# ProPrj_WirelessUWB_2025-08-06.net
KiCad netlist of a schematic drawn in EasyEDA Pro
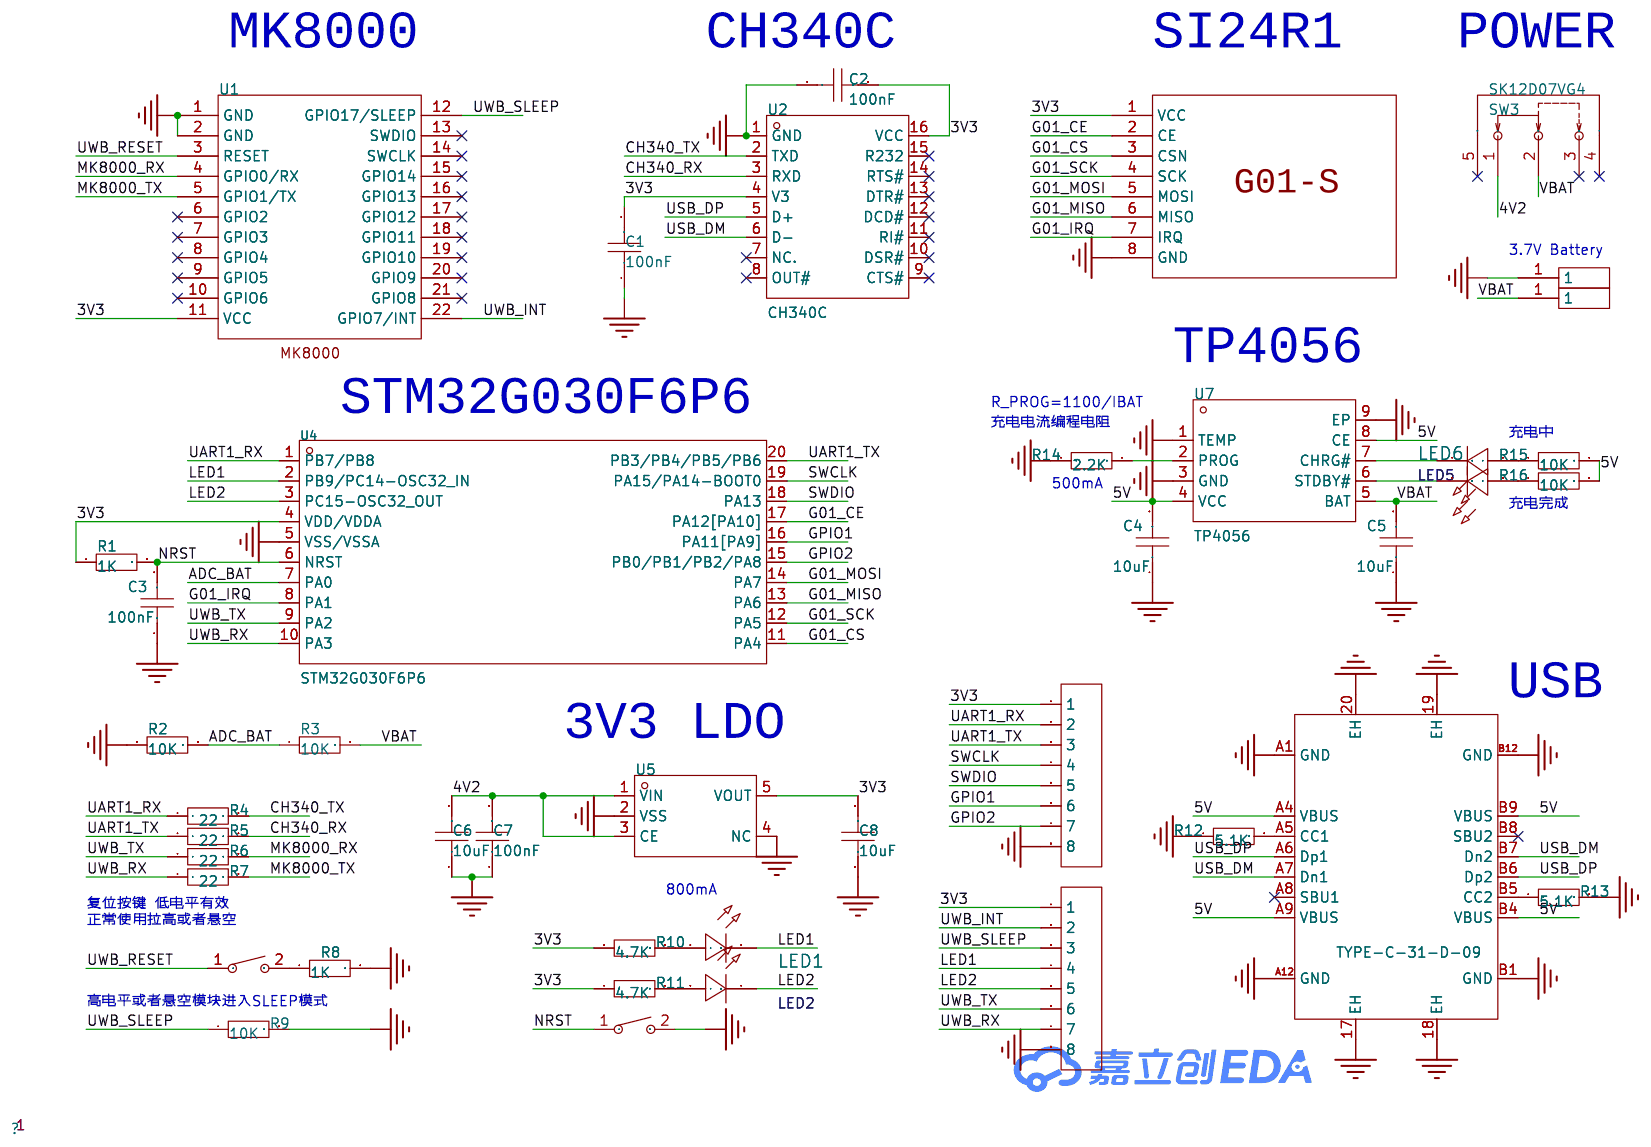
[diagram p0: schematic sheet]

(export (version "E")
  (design (tool "Eeschema 10.0.6"))
  (components
    (comp (ref "C1")
      (value "100nF")
      (footprint "easyedapro:C0603")
      (libsource (lib "easyedapro") (part "CapAcitance"))
    )
    (comp (ref "C2")
      (value "100nF")
      (footprint "easyedapro:C0603")
      (libsource (lib "easyedapro") (part "CapAcitance"))
    )
    (comp (ref "C3")
      (value "100nF")
      (footprint "easyedapro:C0603")
      (libsource (lib "easyedapro") (part "CapAcitance"))
    )
    (comp (ref "C4")
      (value "10uF")
      (footprint "easyedapro:C0603")
      (fields
        (field (name "Manufacturer Part") "CL10A106KP8NNNC")
        (field (name "Manufacturer") "SAMSUNG(三星)")
      )
      (libsource (lib "easyedapro") (part "CapAcitance"))
    )
    (comp (ref "C5")
      (value "10uF")
      (footprint "easyedapro:C0603")
      (fields
        (field (name "Manufacturer Part") "CL10A106KP8NNNC")
        (field (name "Manufacturer") "SAMSUNG(三星)")
      )
      (libsource (lib "easyedapro") (part "CapAcitance"))
    )
    (comp (ref "C6")
      (value "10uF")
      (footprint "easyedapro:C0603")
      (libsource (lib "easyedapro") (part "CapAcitance"))
    )
    (comp (ref "C7")
      (value "100nF")
      (footprint "easyedapro:C0603")
      (libsource (lib "easyedapro") (part "CapAcitance"))
    )
    (comp (ref "C8")
      (value "10uF")
      (footprint "easyedapro:C0603")
      (libsource (lib "easyedapro") (part "CapAcitance"))
    )
    (comp (ref "H1")
      (value "~")
      (footprint "easyedapro:HDR-TH_8P-P2.54-V-F-1")
      (libsource (lib "easyedapro") (part "Header-Female-2.54_1x8"))
    )
    (comp (ref "H2")
      (value "~")
      (footprint "easyedapro:HDR-TH_8P-P2.54-V-F-1")
      (libsource (lib "easyedapro") (part "Header-Female-2.54_1x8"))
    )
    (comp (ref "LED1")
      (value "~")
      (footprint "easyedapro:LED_0603")
      (libsource (lib "easyedapro") (part "LED_R"))
    )
    (comp (ref "LED2")
      (value "~")
      (footprint "easyedapro:LED_0603")
      (libsource (lib "easyedapro") (part "LED_B"))
    )
    (comp (ref "LED5")
      (value "~")
      (footprint "easyedapro:LED_0603")
      (libsource (lib "easyedapro") (part "LED_G"))
    )
    (comp (ref "LED6")
      (value "~")
      (footprint "easyedapro:LED_0603")
      (libsource (lib "easyedapro") (part "LED_R"))
    )
    (comp (ref "R1") (value "1K") (footprint "easyedapro:R0603") (libsource (lib "easyedapro") (part "电阻")))
    (comp (ref "R2") (value "10K") (footprint "easyedapro:R0603") (libsource (lib "easyedapro") (part "电阻")))
    (comp (ref "R3") (value "10K") (footprint "easyedapro:R0603") (libsource (lib "easyedapro") (part "电阻")))
    (comp (ref "R4") (value "22") (footprint "easyedapro:R0603") (libsource (lib "easyedapro") (part "电阻")))
    (comp (ref "R5") (value "22") (footprint "easyedapro:R0603") (libsource (lib "easyedapro") (part "电阻")))
    (comp (ref "R6") (value "22") (footprint "easyedapro:R0603") (libsource (lib "easyedapro") (part "电阻")))
    (comp (ref "R7") (value "22") (footprint "easyedapro:R0603") (libsource (lib "easyedapro") (part "电阻")))
    (comp (ref "R8") (value "1K") (footprint "easyedapro:R0603") (libsource (lib "easyedapro") (part "电阻")))
    (comp (ref "R9") (value "10K") (footprint "easyedapro:R0603") (libsource (lib "easyedapro") (part "电阻")))
    (comp (ref "R10") (value "4.7K") (libsource (lib "easyedapro") (part "电阻")))
    (comp (ref "R11") (value "4.7K") (libsource (lib "easyedapro") (part "电阻")))
    (comp (ref "R12")
      (value "5.1K")
      (footprint "easyedapro:R0603")
      (fields
        (field (name "Manufacturer Part") "0603WAF5101T5E")
        (field (name "Manufacturer") "UNI-ROYAL(厚声)")
      )
      (libsource (lib "easyedapro") (part "电阻"))
    )
    (comp (ref "R13")
      (value "5.1K")
      (footprint "easyedapro:R0603")
      (fields
        (field (name "Manufacturer Part") "0603WAF5101T5E")
        (field (name "Manufacturer") "UNI-ROYAL(厚声)")
      )
      (libsource (lib "easyedapro") (part "电阻"))
    )
    (comp (ref "R14")
      (value "2.2K")
      (footprint "easyedapro:R0603")
      (fields
        (field (name "Manufacturer Part") "0603WAF2201T5E")
        (field (name "Manufacturer") "UNI-ROYAL(厚声)")
      )
      (libsource (lib "easyedapro") (part "电阻"))
    )
    (comp (ref "R15")
      (value "10K")
      (footprint "easyedapro:R0603")
      (fields
        (field (name "Manufacturer Part") "0603WAF1002T5E")
        (field (name "Manufacturer") "UNI-ROYAL(厚声)")
      )
      (libsource (lib "easyedapro") (part "电阻"))
    )
    (comp (ref "R16")
      (value "10K")
      (footprint "easyedapro:R0603")
      (fields
        (field (name "Manufacturer Part") "0603WAF1002T5E")
        (field (name "Manufacturer") "UNI-ROYAL(厚声)")
      )
      (libsource (lib "easyedapro") (part "电阻"))
    )
    (comp (ref "SW1")
      (value "TS342A2P-WZ")
      (footprint "easyedapro:SW-SMD_L4.0-W2.9-LS5.0")
      (fields (field (name "Manufacturer") "SHOU HAN(首韩)"))
      (libsource (lib "easyedapro") (part "TS342A2P-WZ"))
    )
    (comp (ref "SW2")
      (value "TS342A2P-WZ")
      (footprint "easyedapro:SW-SMD_L4.0-W2.9-LS5.0")
      (fields (field (name "Manufacturer") "SHOU HAN(首韩)"))
      (libsource (lib "easyedapro") (part "TS342A2P-WZ"))
    )
    (comp (ref "SW3")
      (value "SK12D07VG4")
      (footprint "easyedapro:SW-TH_SK12D07VG4")
      (description "电路结构:单刀双掷;安装方式:-;额定电流(DC):500mA;额定电压(DC):50V;额定电流(AC):-;额定电压(AC):-;机械寿命:5千次;")
      (fields (field (name "Manufacturer") "SHOU HAN(首韩)"))
      (libsource (lib "easyedapro") (part "SK12D07VG4"))
    )
    (comp (ref "U1")
      (value "~")
      (footprint "easyedapro:MK8000")
      (description "UWB模块")
      (libsource (lib "easyedapro") (part "MK8000"))
    )
    (comp (ref "U2")
      (value "CH340C")
      (footprint "easyedapro:SOP-16_L10.0-W3.9-P1.27-LS6.0-BL")
      (description "应用功能:收发器;接口协议:USB 2.0;数据速率:2Mbps;")
      (fields (field (name "Manufacturer") "WCH(南京沁恒)"))
      (libsource (lib "easyedapro") (part "CH340C"))
    )
    (comp (ref "U3") (value "~") (libsource (lib "easyedapro") (part "G01-S")))
    (comp (ref "U4")
      (value "STM32G030F6P6")
      (footprint "easyedapro:TSSOP-20_L6.5-W4.4-P0.65-LS6.4-BL")
      (description "CPU内核:CM0;程序存储容量:32KB;RAM总容量:8KB;GPIO端口数量:18;工作电压范围:2V~3.6V;CPU最大主频:64MHz;程序存储器类型:FLASH;")
      (fields (field (name "Manufacturer") "ST(意法半导体)"))
      (libsource (lib "easyedapro") (part "STM32G030F6P6"))
    )
    (comp (ref "U5")
      (value "ME6217C33M5G")
      (footprint "easyedapro:SOT-23-5_L3.0-W1.7-P0.95-LS2.8-BR")
      (description "输出类型:固定;输出极性:正;最大输入电压:7V;输出电压:3.3V;输出电流:800mA;电源纹波抑制比(PSRR):65dB@(1kHz);")
      (fields (field (name "Manufacturer") "MICRONE(南京微盟)"))
      (libsource (lib "easyedapro") (part "ME6217C33M5G"))
    )
    (comp (ref "U6")
      (value "TYPE-C-31-D-09")
      (footprint "easyedapro:USB-C-TH_TYPE-C-31-D-09")
      (description "连接器类型:Type-C;公母:母;触点数量:16P;端口数量:1;触头材质:磷青铜;触头镀层:金;工作温度范围:-25°C~+85°C;焊接温度(最大值):255°C;")
      (fields (field (name "Manufacturer") "韩国韩荣"))
      (libsource (lib "easyedapro") (part "TYPE-C-31-D-09_C7463258"))
    )
    (comp (ref "U7")
      (value "TP4056")
      (footprint "easyedapro:ESOP-8_L4.9-W3.9-P1.27-LS6.0-BL-EP")
      (description "工作电压:4V~6V;最大充电电流:1A;电池类型:锂离子/聚合物;电池节数:1;")
      (fields (field (name "Manufacturer") "TPOWER(天源)"))
      (libsource (lib "easyedapro") (part "TP4056_C382139"))
    )
    (comp (ref "U99")
      (value "~")
      (footprint "easyedapro:1pin焊接引出")
      (libsource (lib "easyedapro") (part "1pin焊接引出"))
    )
    (comp (ref "U100")
      (value "~")
      (footprint "easyedapro:1pin焊接引出")
      (libsource (lib "easyedapro") (part "1pin焊接引出"))
    )
  )
  (nets
    (net (code "1") (name "/3V3") (class "Default")
      (node (ref "C1") (pin "2") (pinfunction "2_2") (pintype "input"))
      (node (ref "C2") (pin "2") (pinfunction "2_2") (pintype "input"))
      (node (ref "C8") (pin "2") (pinfunction "2_2") (pintype "input"))
      (node (ref "H1") (pin "1") (pinfunction "1_1") (pintype "input"))
      (node (ref "H2") (pin "1") (pinfunction "1_1") (pintype "input"))
      (node (ref "R1") (pin "1") (pinfunction "1_1") (pintype "input"))
      (node (ref "R10") (pin "1") (pinfunction "1_1") (pintype "input"))
      (node (ref "R11") (pin "1") (pinfunction "1_1") (pintype "input"))
      (node (ref "U1") (pin "11") (pinfunction "VCC_11") (pintype "input"))
      (node (ref "U2") (pin "16") (pinfunction "VCC_16") (pintype "unspecified"))
      (node (ref "U2") (pin "4") (pinfunction "V3_4") (pintype "unspecified"))
      (node (ref "U3") (pin "1") (pinfunction "VCC_1") (pintype "input"))
      (node (ref "U4") (pin "4") (pinfunction "VDD/VDDA_4") (pintype "input"))
      (node (ref "U5") (pin "5") (pinfunction "VOUT_5") (pintype "input"))
    )
    (net (code "2") (name "/4V2") (class "Default")
      (node (ref "C6") (pin "2") (pinfunction "2_2") (pintype "input"))
      (node (ref "C7") (pin "2") (pinfunction "2_2") (pintype "input"))
      (node (ref "SW3") (pin "1") (pinfunction "1_1") (pintype "unspecified"))
      (node (ref "U5") (pin "1") (pinfunction "VIN_1") (pintype "input"))
      (node (ref "U5") (pin "3") (pinfunction "CE_3") (pintype "input"))
    )
    (net (code "3") (name "/5V") (class "Default")
      (node (ref "C4") (pin "2") (pinfunction "2_2") (pintype "input"))
      (node (ref "R15") (pin "2") (pinfunction "2_2") (pintype "input"))
      (node (ref "R16") (pin "2") (pinfunction "2_2") (pintype "input"))
      (node (ref "U6") (pin "A4") (pinfunction "VBUS_A4") (pintype "unspecified"))
      (node (ref "U6") (pin "A9") (pinfunction "VBUS_A9") (pintype "unspecified"))
      (node (ref "U6") (pin "B4") (pinfunction "VBUS_B4") (pintype "unspecified"))
      (node (ref "U6") (pin "B9") (pinfunction "VBUS_B9") (pintype "unspecified"))
      (node (ref "U7") (pin "4") (pinfunction "VCC_4") (pintype "unspecified"))
      (node (ref "U7") (pin "8") (pinfunction "CE_8") (pintype "unspecified"))
    )
    (net (code "4") (name "/ADC_BAT") (class "Default")
      (node (ref "R2") (pin "2") (pinfunction "2_2") (pintype "input"))
      (node (ref "R3") (pin "1") (pinfunction "1_1") (pintype "input"))
      (node (ref "U4") (pin "7") (pinfunction "PA0_7") (pintype "input"))
    )
    (net (code "5") (name "/CH340_RX") (class "Default")
      (node (ref "R5") (pin "2") (pinfunction "2_2") (pintype "input"))
      (node (ref "U2") (pin "3") (pinfunction "RXD_3") (pintype "unspecified"))
    )
    (net (code "6") (name "/CH340_TX") (class "Default")
      (node (ref "R4") (pin "2") (pinfunction "2_2") (pintype "input"))
      (node (ref "U2") (pin "2") (pinfunction "TXD_2") (pintype "unspecified"))
    )
    (net (code "7") (name "/G01_CE") (class "Default")
      (node (ref "U3") (pin "2") (pinfunction "CE_2") (pintype "input"))
      (node (ref "U4") (pin "17") (pinfunction "PA12[PA10]_17") (pintype "input"))
    )
    (net (code "8") (name "/G01_CS") (class "Default")
      (node (ref "U3") (pin "3") (pinfunction "CSN_3") (pintype "input"))
      (node (ref "U4") (pin "11") (pinfunction "PA4_11") (pintype "input"))
    )
    (net (code "9") (name "/G01_IRQ") (class "Default")
      (node (ref "U3") (pin "7") (pinfunction "IRQ_7") (pintype "input"))
      (node (ref "U4") (pin "8") (pinfunction "PA1_8") (pintype "input"))
    )
    (net (code "10") (name "/G01_MISO") (class "Default")
      (node (ref "U3") (pin "6") (pinfunction "MISO_6") (pintype "input"))
      (node (ref "U4") (pin "13") (pinfunction "PA6_13") (pintype "input"))
    )
    (net (code "11") (name "/G01_MOSI") (class "Default")
      (node (ref "U3") (pin "5") (pinfunction "MOSI_5") (pintype "input"))
      (node (ref "U4") (pin "14") (pinfunction "PA7_14") (pintype "input"))
    )
    (net (code "12") (name "/G01_SCK") (class "Default")
      (node (ref "U3") (pin "4") (pinfunction "SCK_4") (pintype "input"))
      (node (ref "U4") (pin "12") (pinfunction "PA5_12") (pintype "input"))
    )
    (net (code "13") (name "/GPIO1") (class "Default")
      (node (ref "H2") (pin "6") (pinfunction "6_6") (pintype "input"))
      (node (ref "U4") (pin "16") (pinfunction "PA11[PA9]_16") (pintype "input"))
    )
    (net (code "14") (name "/GPIO2") (class "Default")
      (node (ref "H2") (pin "7") (pinfunction "7_7") (pintype "input"))
      (node (ref "U4") (pin "15") (pinfunction "PB0/PB1/PB2/PA8_15") (pintype "input"))
    )
    (net (code "15") (name "/LED1") (class "Default")
      (node (ref "H1") (pin "4") (pinfunction "4_4") (pintype "input"))
      (node (ref "LED1") (pin "1") (pinfunction "C_1") (pintype "input"))
      (node (ref "U4") (pin "2") (pinfunction "PB9/PC14-OSC32_IN_2") (pintype "input"))
    )
    (net (code "16") (name "/LED2") (class "Default")
      (node (ref "H1") (pin "5") (pinfunction "5_5") (pintype "input"))
      (node (ref "LED2") (pin "1") (pinfunction "C_1") (pintype "input"))
      (node (ref "U4") (pin "3") (pinfunction "PC15-OSC32_OUT_3") (pintype "input"))
    )
    (net (code "17") (name "/MK8000_RX") (class "Default")
      (node (ref "R6") (pin "2") (pinfunction "2_2") (pintype "input"))
      (node (ref "U1") (pin "4") (pinfunction "GPIO0/RX_4") (pintype "input"))
    )
    (net (code "18") (name "/MK8000_TX") (class "Default")
      (node (ref "R7") (pin "2") (pinfunction "2_2") (pintype "input"))
      (node (ref "U1") (pin "5") (pinfunction "GPIO1/TX_5") (pintype "input"))
    )
    (net (code "19") (name "/NRST") (class "Default")
      (node (ref "C3") (pin "2") (pinfunction "2_2") (pintype "input"))
      (node (ref "R1") (pin "2") (pinfunction "2_2") (pintype "input"))
      (node (ref "SW2") (pin "1") (pinfunction "1_1") (pintype "unspecified"))
      (node (ref "U4") (pin "6") (pinfunction "NRST_6") (pintype "input"))
    )
    (net (code "20") (name "/SWCLK") (class "Default")
      (node (ref "H2") (pin "4") (pinfunction "4_4") (pintype "input"))
      (node (ref "U4") (pin "19") (pinfunction "PA15/PA14-BOOT0_19") (pintype "input"))
    )
    (net (code "21") (name "/SWDIO") (class "Default")
      (node (ref "H2") (pin "5") (pinfunction "5_5") (pintype "input"))
      (node (ref "U4") (pin "18") (pinfunction "PA13_18") (pintype "input"))
    )
    (net (code "22") (name "/UART1_RX") (class "Default")
      (node (ref "H2") (pin "2") (pinfunction "2_2") (pintype "input"))
      (node (ref "R4") (pin "1") (pinfunction "1_1") (pintype "input"))
      (node (ref "U4") (pin "1") (pinfunction "PB7/PB8_1") (pintype "input"))
    )
    (net (code "23") (name "/UART1_TX") (class "Default")
      (node (ref "H2") (pin "3") (pinfunction "3_3") (pintype "input"))
      (node (ref "R5") (pin "1") (pinfunction "1_1") (pintype "input"))
      (node (ref "U4") (pin "20") (pinfunction "PB3/PB4/PB5/PB6_20") (pintype "input"))
    )
    (net (code "24") (name "/USB_DM") (class "Default")
      (node (ref "U2") (pin "6") (pinfunction "D-_6") (pintype "unspecified"))
      (node (ref "U6") (pin "A7") (pinfunction "Dn1_A7") (pintype "unspecified"))
      (node (ref "U6") (pin "B7") (pinfunction "Dn2_B7") (pintype "unspecified"))
    )
    (net (code "25") (name "/USB_DP") (class "Default")
      (node (ref "U2") (pin "5") (pinfunction "D+_5") (pintype "unspecified"))
      (node (ref "U6") (pin "A6") (pinfunction "Dp1_A6") (pintype "unspecified"))
      (node (ref "U6") (pin "B6") (pinfunction "Dp2_B6") (pintype "unspecified"))
    )
    (net (code "26") (name "/UWB_INT") (class "Default")
      (node (ref "H1") (pin "2") (pinfunction "2_2") (pintype "input"))
      (node (ref "U1") (pin "22") (pinfunction "GPIO7/INT_22") (pintype "input"))
    )
    (net (code "27") (name "/UWB_RESET") (class "Default")
      (node (ref "SW1") (pin "1") (pinfunction "1_1") (pintype "unspecified"))
      (node (ref "U1") (pin "3") (pinfunction "RESET_3") (pintype "input"))
    )
    (net (code "28") (name "/UWB_RX") (class "Default")
      (node (ref "H1") (pin "7") (pinfunction "7_7") (pintype "input"))
      (node (ref "R7") (pin "1") (pinfunction "1_1") (pintype "input"))
      (node (ref "U4") (pin "10") (pinfunction "PA3_10") (pintype "input"))
    )
    (net (code "29") (name "/UWB_SLEEP") (class "Default")
      (node (ref "H1") (pin "3") (pinfunction "3_3") (pintype "input"))
      (node (ref "R9") (pin "1") (pinfunction "1_1") (pintype "input"))
      (node (ref "U1") (pin "12") (pinfunction "GPIO17/SLEEP_12") (pintype "input"))
    )
    (net (code "30") (name "/UWB_TX") (class "Default")
      (node (ref "H1") (pin "6") (pinfunction "6_6") (pintype "input"))
      (node (ref "R6") (pin "1") (pinfunction "1_1") (pintype "input"))
      (node (ref "U4") (pin "9") (pinfunction "PA2_9") (pintype "input"))
    )
    (net (code "31") (name "/VBAT") (class "Default")
      (node (ref "C5") (pin "2") (pinfunction "2_2") (pintype "input"))
      (node (ref "R3") (pin "2") (pinfunction "2_2") (pintype "input"))
      (node (ref "SW3") (pin "2") (pinfunction "2_2") (pintype "unspecified"))
      (node (ref "U100") (pin "1") (pinfunction "1_1") (pintype "input"))
      (node (ref "U7") (pin "5") (pinfunction "BAT_5") (pintype "unspecified"))
    )
    (net (code "32") (name "GND") (class "Default")
      (node (ref "C1") (pin "1") (pinfunction "1_1") (pintype "input"))
      (node (ref "C2") (pin "1") (pinfunction "1_1") (pintype "input"))
      (node (ref "C3") (pin "1") (pinfunction "1_1") (pintype "input"))
      (node (ref "C4") (pin "1") (pinfunction "1_1") (pintype "input"))
      (node (ref "C5") (pin "1") (pinfunction "1_1") (pintype "input"))
      (node (ref "C6") (pin "1") (pinfunction "1_1") (pintype "input"))
      (node (ref "C7") (pin "1") (pinfunction "1_1") (pintype "input"))
      (node (ref "C8") (pin "1") (pinfunction "1_1") (pintype "input"))
      (node (ref "H1") (pin "8") (pinfunction "8_8") (pintype "input"))
      (node (ref "H2") (pin "8") (pinfunction "8_8") (pintype "input"))
      (node (ref "R12") (pin "1") (pinfunction "1_1") (pintype "input"))
      (node (ref "R13") (pin "2") (pinfunction "2_2") (pintype "input"))
      (node (ref "R14") (pin "1") (pinfunction "1_1") (pintype "input"))
      (node (ref "R2") (pin "1") (pinfunction "1_1") (pintype "input"))
      (node (ref "R8") (pin "2") (pinfunction "2_2") (pintype "input"))
      (node (ref "R9") (pin "2") (pinfunction "2_2") (pintype "input"))
      (node (ref "SW2") (pin "2") (pinfunction "2_2") (pintype "unspecified"))
      (node (ref "U1") (pin "1") (pinfunction "GND_1") (pintype "input"))
      (node (ref "U1") (pin "2") (pinfunction "GND_2") (pintype "input"))
      (node (ref "U2") (pin "1") (pinfunction "GND_1") (pintype "unspecified"))
      (node (ref "U3") (pin "8") (pinfunction "GND_8") (pintype "input"))
      (node (ref "U4") (pin "5") (pinfunction "VSS/VSSA_5") (pintype "input"))
      (node (ref "U5") (pin "2") (pinfunction "VSS_2") (pintype "input"))
      (node (ref "U5") (pin "4") (pinfunction "NC_4") (pintype "input"))
      (node (ref "U6") (pin "17") (pinfunction "EH_17") (pintype "unspecified"))
      (node (ref "U6") (pin "18") (pinfunction "EH_18") (pintype "unspecified"))
      (node (ref "U6") (pin "19") (pinfunction "EH_19") (pintype "unspecified"))
      (node (ref "U6") (pin "20") (pinfunction "EH_20") (pintype "unspecified"))
      (node (ref "U6") (pin "A1") (pinfunction "GND_A1") (pintype "unspecified"))
      (node (ref "U6") (pin "A12") (pinfunction "GND_A12") (pintype "unspecified"))
      (node (ref "U6") (pin "B1") (pinfunction "GND_B1") (pintype "unspecified"))
      (node (ref "U6") (pin "B12") (pinfunction "GND_B12") (pintype "unspecified"))
      (node (ref "U7") (pin "1") (pinfunction "TEMP_1") (pintype "unspecified"))
      (node (ref "U7") (pin "3") (pinfunction "GND_3") (pintype "unspecified"))
      (node (ref "U7") (pin "9") (pinfunction "EP_9") (pintype "unspecified"))
      (node (ref "U99") (pin "1") (pinfunction "1_1") (pintype "input"))
    )
    (net (code "33") (name "Net-(LED1-A)") (class "Default")
      (node (ref "LED1") (pin "2") (pinfunction "A_2") (pintype "input"))
      (node (ref "R10") (pin "2") (pinfunction "2_2") (pintype "input"))
    )
    (net (code "34") (name "Net-(LED2-A)") (class "Default")
      (node (ref "LED2") (pin "2") (pinfunction "A_2") (pintype "input"))
      (node (ref "R11") (pin "2") (pinfunction "2_2") (pintype "input"))
    )
    (net (code "35") (name "Net-(LED5-A)") (class "Default")
      (node (ref "LED5") (pin "2") (pinfunction "A_2") (pintype "input"))
      (node (ref "R16") (pin "1") (pinfunction "1_1") (pintype "input"))
    )
    (net (code "36") (name "Net-(LED5-C)") (class "Default")
      (node (ref "LED5") (pin "1") (pinfunction "C_1") (pintype "input"))
      (node (ref "U7") (pin "6") (pinfunction "STDBY#_6") (pintype "unspecified"))
    )
    (net (code "37") (name "Net-(LED6-A)") (class "Default")
      (node (ref "LED6") (pin "2") (pinfunction "A_2") (pintype "input"))
      (node (ref "R15") (pin "1") (pinfunction "1_1") (pintype "input"))
    )
    (net (code "38") (name "Net-(LED6-C)") (class "Default")
      (node (ref "LED6") (pin "1") (pinfunction "C_1") (pintype "input"))
      (node (ref "U7") (pin "7") (pinfunction "CHRG#_7") (pintype "unspecified"))
    )
    (net (code "39") (name "Net-(R8-Pad1)") (class "Default")
      (node (ref "R8") (pin "1") (pinfunction "1_1") (pintype "input"))
      (node (ref "SW1") (pin "2") (pinfunction "2_2") (pintype "unspecified"))
    )
    (net (code "40") (name "Net-(U6-CC1)") (class "Default")
      (node (ref "R12") (pin "2") (pinfunction "2_2") (pintype "input"))
      (node (ref "U6") (pin "A5") (pinfunction "CC1_A5") (pintype "unspecified"))
    )
    (net (code "41") (name "Net-(U6-CC2)") (class "Default")
      (node (ref "R13") (pin "1") (pinfunction "1_1") (pintype "input"))
      (node (ref "U6") (pin "B5") (pinfunction "CC2_B5") (pintype "unspecified"))
    )
    (net (code "42") (name "Net-(U7-PROG)") (class "Default")
      (node (ref "R14") (pin "2") (pinfunction "2_2") (pintype "input"))
      (node (ref "U7") (pin "2") (pinfunction "PROG_2") (pintype "unspecified"))
    )
    (net (code "43") (name "unconnected-(SW3-Pad3)") (class "Default")
      (node (ref "SW3") (pin "3") (pinfunction "3_3") (pintype "unspecified+no_connect"))
    )
    (net (code "44") (name "unconnected-(SW3-Pad4)") (class "Default")
      (node (ref "SW3") (pin "4") (pinfunction "4_4") (pintype "unspecified+no_connect"))
    )
    (net (code "45") (name "unconnected-(SW3-Pad5)") (class "Default")
      (node (ref "SW3") (pin "5") (pinfunction "5_5") (pintype "unspecified+no_connect"))
    )
    (net (code "46") (name "unconnected-(U1-GPIO2-Pad6)") (class "Default")
      (node (ref "U1") (pin "6") (pinfunction "GPIO2_6") (pintype "input+no_connect"))
    )
    (net (code "47") (name "unconnected-(U1-GPIO3-Pad7)") (class "Default")
      (node (ref "U1") (pin "7") (pinfunction "GPIO3_7") (pintype "input+no_connect"))
    )
    (net (code "48") (name "unconnected-(U1-GPIO4-Pad8)") (class "Default")
      (node (ref "U1") (pin "8") (pinfunction "GPIO4_8") (pintype "input+no_connect"))
    )
    (net (code "49") (name "unconnected-(U1-GPIO5-Pad9)") (class "Default")
      (node (ref "U1") (pin "9") (pinfunction "GPIO5_9") (pintype "input+no_connect"))
    )
    (net (code "50") (name "unconnected-(U1-GPIO6-Pad10)") (class "Default")
      (node (ref "U1") (pin "10") (pinfunction "GPIO6_10") (pintype "input+no_connect"))
    )
    (net (code "51") (name "unconnected-(U1-GPIO8-Pad21)") (class "Default")
      (node (ref "U1") (pin "21") (pinfunction "GPIO8_21") (pintype "input+no_connect"))
    )
    (net (code "52") (name "unconnected-(U1-GPIO9-Pad20)") (class "Default")
      (node (ref "U1") (pin "20") (pinfunction "GPIO9_20") (pintype "input+no_connect"))
    )
    (net (code "53") (name "unconnected-(U1-GPIO10-Pad19)") (class "Default")
      (node (ref "U1") (pin "19") (pinfunction "GPIO10_19") (pintype "input+no_connect"))
    )
    (net (code "54") (name "unconnected-(U1-GPIO11-Pad18)") (class "Default")
      (node (ref "U1") (pin "18") (pinfunction "GPIO11_18") (pintype "input+no_connect"))
    )
    (net (code "55") (name "unconnected-(U1-GPIO12-Pad17)") (class "Default")
      (node (ref "U1") (pin "17") (pinfunction "GPIO12_17") (pintype "input+no_connect"))
    )
    (net (code "56") (name "unconnected-(U1-GPIO13-Pad16)") (class "Default")
      (node (ref "U1") (pin "16") (pinfunction "GPIO13_16") (pintype "input+no_connect"))
    )
    (net (code "57") (name "unconnected-(U1-GPIO14-Pad15)") (class "Default")
      (node (ref "U1") (pin "15") (pinfunction "GPIO14_15") (pintype "input+no_connect"))
    )
    (net (code "58") (name "unconnected-(U1-SWCLK-Pad14)") (class "Default")
      (node (ref "U1") (pin "14") (pinfunction "SWCLK_14") (pintype "input+no_connect"))
    )
    (net (code "59") (name "unconnected-(U1-SWDIO-Pad13)") (class "Default")
      (node (ref "U1") (pin "13") (pinfunction "SWDIO_13") (pintype "input+no_connect"))
    )
    (net (code "60") (name "unconnected-(U2-CTS#-Pad9)") (class "Default")
      (node (ref "U2") (pin "9") (pinfunction "CTS#_9") (pintype "unspecified+no_connect"))
    )
    (net (code "61") (name "unconnected-(U2-DCD#-Pad12)") (class "Default")
      (node (ref "U2") (pin "12") (pinfunction "DCD#_12") (pintype "unspecified+no_connect"))
    )
    (net (code "62") (name "unconnected-(U2-DSR#-Pad10)") (class "Default")
      (node (ref "U2") (pin "10") (pinfunction "DSR#_10") (pintype "unspecified+no_connect"))
    )
    (net (code "63") (name "unconnected-(U2-DTR#-Pad13)") (class "Default")
      (node (ref "U2") (pin "13") (pinfunction "DTR#_13") (pintype "unspecified+no_connect"))
    )
    (net (code "64") (name "unconnected-(U2-NC.-Pad7)") (class "Default")
      (node (ref "U2") (pin "7") (pinfunction "NC._7") (pintype "unspecified+no_connect"))
    )
    (net (code "65") (name "unconnected-(U2-OUT#-Pad8)") (class "Default")
      (node (ref "U2") (pin "8") (pinfunction "OUT#_8") (pintype "unspecified+no_connect"))
    )
    (net (code "66") (name "unconnected-(U2-R232-Pad15)") (class "Default")
      (node (ref "U2") (pin "15") (pinfunction "R232_15") (pintype "unspecified+no_connect"))
    )
    (net (code "67") (name "unconnected-(U2-RI#-Pad11)") (class "Default")
      (node (ref "U2") (pin "11") (pinfunction "RI#_11") (pintype "unspecified+no_connect"))
    )
    (net (code "68") (name "unconnected-(U2-RTS#-Pad14)") (class "Default")
      (node (ref "U2") (pin "14") (pinfunction "RTS#_14") (pintype "unspecified+no_connect"))
    )
    (net (code "69") (name "unconnected-(U6-SBU1-PadA8)") (class "Default")
      (node (ref "U6") (pin "A8") (pinfunction "SBU1_A8") (pintype "unspecified+no_connect"))
    )
    (net (code "70") (name "unconnected-(U6-SBU2-PadB8)") (class "Default")
      (node (ref "U6") (pin "B8") (pinfunction "SBU2_B8") (pintype "unspecified+no_connect"))
    )
  )
)
